# Probe-Scope_AFE_v1_0.net
KiCad netlist of a schematic drawn in Altium Designer
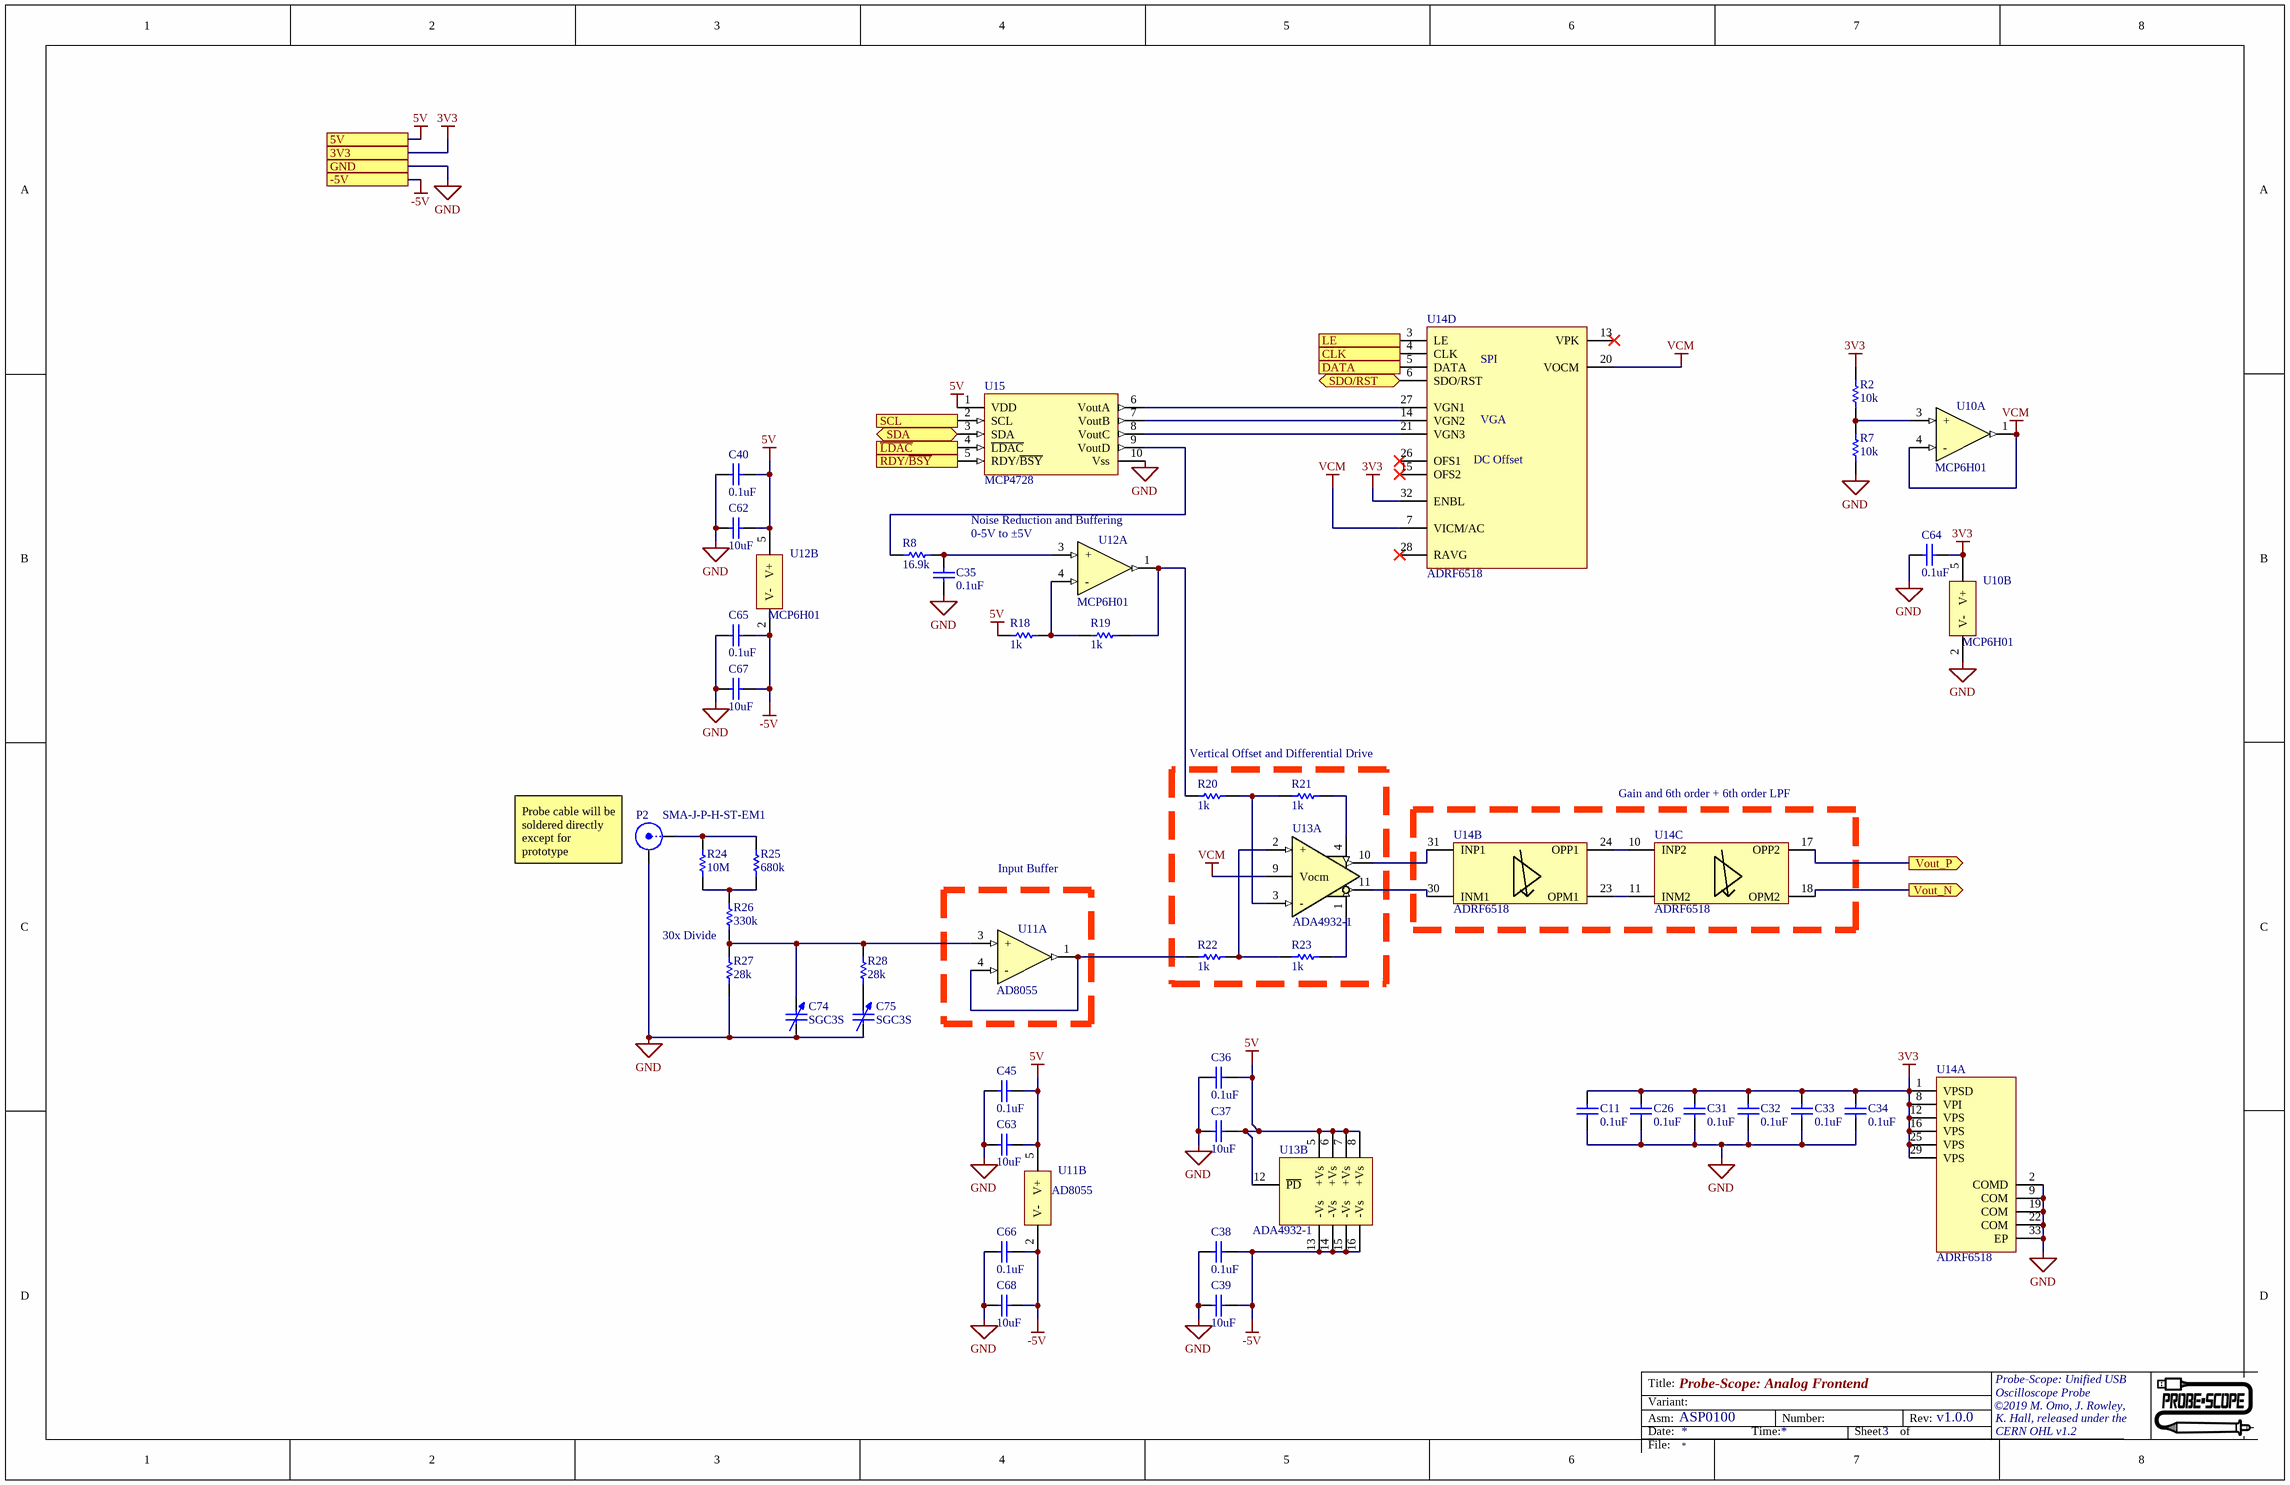
[diagram p0: Probe-Scope AFE v1.0.SchDoc]

(export (version "E")
  (design (tool "Eeschema 10.0.6"))
  (components
    (comp (ref "C11")
      (value "0.1uF")
      (footprint "0402(1005)")
      (fields
        (field (name "MANF") "Samsung Electro-Mechanics")
        (field (name "TOLERANCE") "10")
        (field (name "VOLTAGE") "6.3")
        (field (name "MODIFIED BY") "jrowley")
        (field (name "APPROVED") "False")
      )
      (libsource (lib "MENG Database Library VPN") (part "Cap"))
    )
    (comp (ref "C26")
      (value "0.1uF")
      (footprint "0402(1005)")
      (fields
        (field (name "MANF") "Samsung Electro-Mechanics")
        (field (name "TOLERANCE") "10")
        (field (name "VOLTAGE") "6.3")
        (field (name "MODIFIED BY") "jrowley")
        (field (name "APPROVED") "False")
      )
      (libsource (lib "MENG Database Library VPN") (part "Cap"))
    )
    (comp (ref "C31")
      (value "0.1uF")
      (footprint "0402(1005)")
      (fields
        (field (name "MANF") "Samsung Electro-Mechanics")
        (field (name "TOLERANCE") "10")
        (field (name "VOLTAGE") "6.3")
        (field (name "MODIFIED BY") "jrowley")
        (field (name "APPROVED") "False")
      )
      (libsource (lib "MENG Database Library VPN") (part "Cap"))
    )
    (comp (ref "C32")
      (value "0.1uF")
      (footprint "0402(1005)")
      (fields
        (field (name "MANF") "Samsung Electro-Mechanics")
        (field (name "TOLERANCE") "10")
        (field (name "VOLTAGE") "6.3")
        (field (name "MODIFIED BY") "jrowley")
        (field (name "APPROVED") "False")
      )
      (libsource (lib "MENG Database Library VPN") (part "Cap"))
    )
    (comp (ref "C33")
      (value "0.1uF")
      (footprint "0402(1005)")
      (fields
        (field (name "MANF") "Samsung Electro-Mechanics")
        (field (name "TOLERANCE") "10")
        (field (name "VOLTAGE") "6.3")
        (field (name "MODIFIED BY") "jrowley")
        (field (name "APPROVED") "False")
      )
      (libsource (lib "MENG Database Library VPN") (part "Cap"))
    )
    (comp (ref "C34")
      (value "0.1uF")
      (footprint "0402(1005)")
      (fields
        (field (name "MANF") "Samsung Electro-Mechanics")
        (field (name "TOLERANCE") "10")
        (field (name "VOLTAGE") "6.3")
        (field (name "MODIFIED BY") "jrowley")
        (field (name "APPROVED") "False")
      )
      (libsource (lib "MENG Database Library VPN") (part "Cap"))
    )
    (comp (ref "C35")
      (value "0.1uF")
      (footprint "0402(1005)")
      (fields
        (field (name "MANF") "Samsung Electro-Mechanics")
        (field (name "TOLERANCE") "10")
        (field (name "VOLTAGE") "6.3")
        (field (name "MODIFIED BY") "jrowley")
        (field (name "APPROVED") "False")
      )
      (libsource (lib "MENG Database Library VPN") (part "Cap"))
    )
    (comp (ref "C36")
      (value "0.1uF")
      (footprint "0402(1005)")
      (fields
        (field (name "MANF") "Samsung Electro-Mechanics")
        (field (name "TOLERANCE") "10")
        (field (name "VOLTAGE") "6.3")
        (field (name "MODIFIED BY") "jrowley")
        (field (name "APPROVED") "False")
      )
      (libsource (lib "MENG Database Library VPN") (part "Cap"))
    )
    (comp (ref "C37")
      (value "10uF")
      (footprint "0603(1608)")
      (fields
        (field (name "MANF") "Samsung Electro-Mechanics")
        (field (name "TOLERANCE") "20")
        (field (name "VOLTAGE") "25")
        (field (name "MODIFIED BY") "sotterbacher")
        (field (name "APPROVED") "True")
      )
      (libsource (lib "MENG Database Library VPN") (part "Cap"))
    )
    (comp (ref "C38")
      (value "0.1uF")
      (footprint "0402(1005)")
      (fields
        (field (name "MANF") "Samsung Electro-Mechanics")
        (field (name "TOLERANCE") "10")
        (field (name "VOLTAGE") "6.3")
        (field (name "MODIFIED BY") "jrowley")
        (field (name "APPROVED") "False")
      )
      (libsource (lib "MENG Database Library VPN") (part "Cap"))
    )
    (comp (ref "C39")
      (value "10uF")
      (footprint "0603(1608)")
      (fields
        (field (name "MANF") "Samsung Electro-Mechanics")
        (field (name "TOLERANCE") "20")
        (field (name "VOLTAGE") "25")
        (field (name "MODIFIED BY") "sotterbacher")
        (field (name "APPROVED") "True")
      )
      (libsource (lib "MENG Database Library VPN") (part "Cap"))
    )
    (comp (ref "C40")
      (value "0.1uF")
      (footprint "0402(1005)")
      (fields
        (field (name "MANF") "Samsung Electro-Mechanics")
        (field (name "TOLERANCE") "10")
        (field (name "VOLTAGE") "6.3")
        (field (name "MODIFIED BY") "jrowley")
        (field (name "APPROVED") "False")
      )
      (libsource (lib "MENG Database Library VPN") (part "Cap"))
    )
    (comp (ref "C45")
      (value "0.1uF")
      (footprint "0402(1005)")
      (fields
        (field (name "MANF") "Samsung Electro-Mechanics")
        (field (name "TOLERANCE") "10")
        (field (name "VOLTAGE") "6.3")
        (field (name "MODIFIED BY") "jrowley")
        (field (name "APPROVED") "False")
      )
      (libsource (lib "MENG Database Library VPN") (part "Cap"))
    )
    (comp (ref "C62")
      (value "10uF")
      (footprint "0603(1608)")
      (fields
        (field (name "MANF") "Samsung Electro-Mechanics")
        (field (name "TOLERANCE") "20")
        (field (name "VOLTAGE") "25")
        (field (name "MODIFIED BY") "sotterbacher")
        (field (name "APPROVED") "True")
      )
      (libsource (lib "MENG Database Library VPN") (part "Cap"))
    )
    (comp (ref "C63")
      (value "10uF")
      (footprint "0603(1608)")
      (fields
        (field (name "MANF") "Samsung Electro-Mechanics")
        (field (name "TOLERANCE") "20")
        (field (name "VOLTAGE") "25")
        (field (name "MODIFIED BY") "sotterbacher")
        (field (name "APPROVED") "True")
      )
      (libsource (lib "MENG Database Library VPN") (part "Cap"))
    )
    (comp (ref "C64")
      (value "0.1uF")
      (footprint "0402(1005)")
      (fields
        (field (name "MANF") "Samsung Electro-Mechanics")
        (field (name "TOLERANCE") "10")
        (field (name "VOLTAGE") "6.3")
        (field (name "MODIFIED BY") "jrowley")
        (field (name "APPROVED") "False")
      )
      (libsource (lib "MENG Database Library VPN") (part "Cap"))
    )
    (comp (ref "C65")
      (value "0.1uF")
      (footprint "0402(1005)")
      (fields
        (field (name "MANF") "Samsung Electro-Mechanics")
        (field (name "TOLERANCE") "10")
        (field (name "VOLTAGE") "6.3")
        (field (name "MODIFIED BY") "jrowley")
        (field (name "APPROVED") "False")
      )
      (libsource (lib "MENG Database Library VPN") (part "Cap"))
    )
    (comp (ref "C66")
      (value "0.1uF")
      (footprint "0402(1005)")
      (fields
        (field (name "MANF") "Samsung Electro-Mechanics")
        (field (name "TOLERANCE") "10")
        (field (name "VOLTAGE") "6.3")
        (field (name "MODIFIED BY") "jrowley")
        (field (name "APPROVED") "False")
      )
      (libsource (lib "MENG Database Library VPN") (part "Cap"))
    )
    (comp (ref "C67")
      (value "10uF")
      (footprint "0603(1608)")
      (fields
        (field (name "MANF") "Samsung Electro-Mechanics")
        (field (name "TOLERANCE") "20")
        (field (name "VOLTAGE") "25")
        (field (name "MODIFIED BY") "sotterbacher")
        (field (name "APPROVED") "True")
      )
      (libsource (lib "MENG Database Library VPN") (part "Cap"))
    )
    (comp (ref "C68")
      (value "10uF")
      (footprint "0603(1608)")
      (fields
        (field (name "MANF") "Samsung Electro-Mechanics")
        (field (name "TOLERANCE") "20")
        (field (name "VOLTAGE") "25")
        (field (name "MODIFIED BY") "sotterbacher")
        (field (name "APPROVED") "True")
      )
      (libsource (lib "MENG Database Library VPN") (part "Cap"))
    )
    (comp (ref "C74") (value "SGC3S") (footprint "SGC3S") (libsource (lib "SE2D v1.0") (part "VarCap")))
    (comp (ref "C75") (value "SGC3S") (footprint "SGC3S") (libsource (lib "SE2D v1.0") (part "VarCap")))
    (comp (ref "P2")
      (value "SMA-J-P-H-ST-EM1")
      (footprint "SE2D v1.0:*SMA-J-P-H-ST-EM1_SMA-J-P-H-ST-EM1(Primary)")
      (fields (field (name "MANF") "Samtec Inc."))
      (libsource (lib "SE2D v1.0") (part "SMA-J-P-H-ST-EM1"))
    )
    (comp (ref "R2")
      (value "10k")
      (footprint "0402(1005)")
      (fields
        (field (name "MANF") "Stackpole Electronics")
        (field (name "TOLERANCE") "1")
        (field (name "POWER") "0.0625")
        (field (name "MODIFIED BY") "jrowley")
        (field (name "APPROVED") "False")
      )
      (libsource (lib "MENG Database Library VPN") (part "Res1"))
    )
    (comp (ref "R7")
      (value "10k")
      (footprint "0402(1005)")
      (fields
        (field (name "MANF") "Stackpole Electronics")
        (field (name "TOLERANCE") "1")
        (field (name "POWER") "0.0625")
        (field (name "MODIFIED BY") "jrowley")
        (field (name "APPROVED") "False")
      )
      (libsource (lib "MENG Database Library VPN") (part "Res1"))
    )
    (comp (ref "R8")
      (value "16.9k")
      (footprint "0603(1608)")
      (fields
        (field (name "MANF") "Panasonic")
        (field (name "TOLERANCE") "1")
        (field (name "POWER") "0.1")
        (field (name "MODIFIED BY") "sotterbacher")
        (field (name "APPROVED") "True")
      )
      (libsource (lib "MENG Database Library VPN") (part "Res1"))
    )
    (comp (ref "R18")
      (value "1k")
      (footprint "0402(1005)")
      (fields
        (field (name "MANF") "Yageo")
        (field (name "TOLERANCE") "1")
        (field (name "POWER") "0.063")
        (field (name "MODIFIED BY") "jrowley")
        (field (name "APPROVED") "False")
      )
      (libsource (lib "MENG Database Library VPN") (part "Res1"))
    )
    (comp (ref "R19")
      (value "1k")
      (footprint "0402(1005)")
      (fields
        (field (name "MANF") "Yageo")
        (field (name "TOLERANCE") "1")
        (field (name "POWER") "0.063")
        (field (name "MODIFIED BY") "jrowley")
        (field (name "APPROVED") "False")
      )
      (libsource (lib "MENG Database Library VPN") (part "Res1"))
    )
    (comp (ref "R20")
      (value "1k")
      (footprint "0402(1005)")
      (fields
        (field (name "MANF") "Yageo")
        (field (name "TOLERANCE") "1")
        (field (name "POWER") "0.063")
        (field (name "MODIFIED BY") "jrowley")
        (field (name "APPROVED") "False")
      )
      (libsource (lib "MENG Database Library VPN") (part "Res1"))
    )
    (comp (ref "R21")
      (value "1k")
      (footprint "0402(1005)")
      (fields
        (field (name "MANF") "Yageo")
        (field (name "TOLERANCE") "1")
        (field (name "POWER") "0.063")
        (field (name "MODIFIED BY") "jrowley")
        (field (name "APPROVED") "False")
      )
      (libsource (lib "MENG Database Library VPN") (part "Res1"))
    )
    (comp (ref "R22")
      (value "1k")
      (footprint "0402(1005)")
      (fields
        (field (name "MANF") "Yageo")
        (field (name "TOLERANCE") "1")
        (field (name "POWER") "0.063")
        (field (name "MODIFIED BY") "jrowley")
        (field (name "APPROVED") "False")
      )
      (libsource (lib "MENG Database Library VPN") (part "Res1"))
    )
    (comp (ref "R23")
      (value "1k")
      (footprint "0402(1005)")
      (fields
        (field (name "MANF") "Yageo")
        (field (name "TOLERANCE") "1")
        (field (name "POWER") "0.063")
        (field (name "MODIFIED BY") "jrowley")
        (field (name "APPROVED") "False")
      )
      (libsource (lib "MENG Database Library VPN") (part "Res1"))
    )
    (comp (ref "R24")
      (value "10M")
      (footprint "0402(1005)")
      (fields
        (field (name "MANF") "Vishay Dale")
        (field (name "TOLERANCE") "1")
        (field (name "POWER") "0.063")
        (field (name "MODIFIED BY") "momo")
        (field (name "APPROVED") "False")
      )
      (libsource (lib "MENG Database Library VPN") (part "Res1"))
    )
    (comp (ref "R25")
      (value "680k")
      (footprint "0402(1005)")
      (fields
        (field (name "MANF") "Vishay Dale")
        (field (name "TOLERANCE") "1")
        (field (name "POWER") "0.063")
        (field (name "MODIFIED BY") "momo")
        (field (name "APPROVED") "False")
      )
      (libsource (lib "MENG Database Library VPN") (part "Res1"))
    )
    (comp (ref "R26")
      (value "330k")
      (footprint "0402(1005)")
      (fields
        (field (name "MANF") "Vishay Dale")
        (field (name "TOLERANCE") "1")
        (field (name "POWER") "0.2")
        (field (name "MODIFIED BY") "momo")
        (field (name "APPROVED") "False")
      )
      (libsource (lib "MENG Database Library VPN") (part "Res1"))
    )
    (comp (ref "R27")
      (value "28k")
      (footprint "0402(1005)")
      (fields
        (field (name "MANF") "Vishay Dale")
        (field (name "TOLERANCE") "1")
        (field (name "POWER") "0.063")
        (field (name "MODIFIED BY") "momo")
        (field (name "APPROVED") "False")
      )
      (libsource (lib "MENG Database Library VPN") (part "Res1"))
    )
    (comp (ref "R28")
      (value "28k")
      (footprint "0402(1005)")
      (fields
        (field (name "MANF") "Vishay Dale")
        (field (name "TOLERANCE") "1")
        (field (name "POWER") "0.063")
        (field (name "MODIFIED BY") "momo")
        (field (name "APPROVED") "False")
      )
      (libsource (lib "MENG Database Library VPN") (part "Res1"))
    )
    (comp (ref "U10")
      (value "MCP6H01")
      (footprint "SOT23-5")
      (fields
        (field (name "MANF") "Microchip")
        (field (name "MODIFIED BY") "momo")
        (field (name "APPROVED") "False")
      )
      (libsource (lib "MENG Database Library VPN") (part "Opamp Single SOT23-5"))
    )
    (comp (ref "U11")
      (value "AD8055")
      (footprint "SOT95P280X145-5L")
      (fields (field (name "MANF") "Analog Devices Inc."))
      (libsource (lib "PS v1.0") (part "AD8055"))
    )
    (comp (ref "U12")
      (value "MCP6H01")
      (footprint "SOT23-5")
      (fields
        (field (name "MANF") "Microchip")
        (field (name "MODIFIED BY") "momo")
        (field (name "APPROVED") "False")
      )
      (libsource (lib "MENG Database Library VPN") (part "Opamp Single SOT23-5"))
    )
    (comp (ref "U13")
      (value "ADA4932-1")
      (footprint "QFN50P300X300X80_HS-17L")
      (fields (field (name "MANF") "Analog Devices Inc."))
      (libsource (lib "PS v1.0") (part "ADA4932"))
    )
    (comp (ref "U14")
      (value "ADRF6518")
      (footprint "QFN50P500X500X80_HS-33L")
      (fields (field (name "MANF") "Analog Devices Inc."))
      (libsource (lib "PS v1.0") (part "ADRF6518"))
    )
    (comp (ref "U15")
      (value "MCP4728")
      (footprint "MSOP-10")
      (fields (field (name "MANF") "Microchip Technology"))
      (libsource (lib "PS v1.0") (part "MCP4728"))
    )
  )
  (nets
    (net (code "1") (name "-5V") (class "Default")
      (node (ref "C38") (pin "2") (pinfunction "2_2") (pintype "passive"))
      (node (ref "C39") (pin "2") (pinfunction "2_2") (pintype "passive"))
      (node (ref "C65") (pin "2") (pinfunction "2_2") (pintype "passive"))
      (node (ref "C66") (pin "2") (pinfunction "2_2") (pintype "passive"))
      (node (ref "C67") (pin "2") (pinfunction "2_2") (pintype "passive"))
      (node (ref "C68") (pin "2") (pinfunction "2_2") (pintype "passive"))
      (node (ref "U11") (pin "2") (pinfunction "V-_2") (pintype "power_in"))
      (node (ref "U12") (pin "2") (pinfunction "V-_2") (pintype "power_in"))
      (node (ref "U13") (pin "13") (pinfunction "-Vs_13") (pintype "power_in"))
      (node (ref "U13") (pin "14") (pinfunction "-Vs_14") (pintype "power_in"))
      (node (ref "U13") (pin "15") (pinfunction "-Vs_15") (pintype "power_in"))
      (node (ref "U13") (pin "16") (pinfunction "-Vs_16") (pintype "power_in"))
    )
    (net (code "2") (name "/CLK") (class "Default")
      (node (ref "U14") (pin "4") (pinfunction "CLK_4") (pintype "passive"))
    )
    (net (code "3") (name "/DATA") (class "Default")
      (node (ref "U14") (pin "5") (pinfunction "DATA_5") (pintype "passive"))
    )
    (net (code "4") (name "/LE") (class "Default")
      (node (ref "U14") (pin "3") (pinfunction "LE_3") (pintype "passive"))
    )
    (net (code "5") (name "/RDY{slash}~{BSY}") (class "Default")
      (node (ref "U15") (pin "5") (pinfunction "RDY/~{BSY}_5") (pintype "input"))
    )
    (net (code "6") (name "/SCL") (class "Default")
      (node (ref "U15") (pin "2") (pinfunction "SCL_2") (pintype "input"))
    )
    (net (code "7") (name "/SDA") (class "Default")
      (node (ref "U15") (pin "3") (pinfunction "SDA_3") (pintype "input"))
    )
    (net (code "8") (name "/SDO{slash}RST") (class "Default")
      (node (ref "U14") (pin "6") (pinfunction "SDO/RST_6") (pintype "passive"))
    )
    (net (code "9") (name "/Vout_N") (class "Default")
      (node (ref "U14") (pin "18") (pinfunction "OPM2_18") (pintype "passive"))
    )
    (net (code "10") (name "/Vout_P") (class "Default")
      (node (ref "U14") (pin "17") (pinfunction "OPP2_17") (pintype "passive"))
    )
    (net (code "11") (name "/~{LDAC}") (class "Default")
      (node (ref "U15") (pin "4") (pinfunction "~{LDAC}_4") (pintype "input"))
    )
    (net (code "12") (name "3V3") (class "Default")
      (node (ref "C11") (pin "2") (pinfunction "2_2") (pintype "passive"))
      (node (ref "C26") (pin "2") (pinfunction "2_2") (pintype "passive"))
      (node (ref "C31") (pin "2") (pinfunction "2_2") (pintype "passive"))
      (node (ref "C32") (pin "2") (pinfunction "2_2") (pintype "passive"))
      (node (ref "C33") (pin "2") (pinfunction "2_2") (pintype "passive"))
      (node (ref "C34") (pin "2") (pinfunction "2_2") (pintype "passive"))
      (node (ref "C64") (pin "2") (pinfunction "2_2") (pintype "passive"))
      (node (ref "R2") (pin "2") (pinfunction "2_2") (pintype "passive"))
      (node (ref "U10") (pin "5") (pinfunction "V+_5") (pintype "power_in"))
      (node (ref "U14") (pin "1") (pinfunction "VPSD_1") (pintype "passive"))
      (node (ref "U14") (pin "12") (pinfunction "VPS_12") (pintype "passive"))
      (node (ref "U14") (pin "16") (pinfunction "VPS_16") (pintype "passive"))
      (node (ref "U14") (pin "25") (pinfunction "VPS_25") (pintype "passive"))
      (node (ref "U14") (pin "29") (pinfunction "VPS_29") (pintype "passive"))
      (node (ref "U14") (pin "32") (pinfunction "ENBL_32") (pintype "passive"))
      (node (ref "U14") (pin "8") (pinfunction "VPI_8") (pintype "passive"))
    )
    (net (code "13") (name "5V") (class "Default")
      (node (ref "C36") (pin "2") (pinfunction "2_2") (pintype "passive"))
      (node (ref "C37") (pin "2") (pinfunction "2_2") (pintype "passive"))
      (node (ref "C40") (pin "2") (pinfunction "2_2") (pintype "passive"))
      (node (ref "C45") (pin "2") (pinfunction "2_2") (pintype "passive"))
      (node (ref "C62") (pin "2") (pinfunction "2_2") (pintype "passive"))
      (node (ref "C63") (pin "2") (pinfunction "2_2") (pintype "passive"))
      (node (ref "R18") (pin "1") (pinfunction "1_1") (pintype "passive"))
      (node (ref "U11") (pin "5") (pinfunction "V+_5") (pintype "power_in"))
      (node (ref "U12") (pin "5") (pinfunction "V+_5") (pintype "power_in"))
      (node (ref "U13") (pin "12") (pinfunction "~{PD}_12") (pintype "power_in"))
      (node (ref "U13") (pin "5") (pinfunction "+Vs_5") (pintype "power_in"))
      (node (ref "U13") (pin "6") (pinfunction "+Vs_6") (pintype "power_in"))
      (node (ref "U13") (pin "7") (pinfunction "+Vs_7") (pintype "power_in"))
      (node (ref "U13") (pin "8") (pinfunction "+Vs_8") (pintype "power_in"))
      (node (ref "U15") (pin "1") (pinfunction "VDD_1") (pintype "power_in"))
    )
    (net (code "14") (name "GND") (class "Default")
      (node (ref "C11") (pin "1") (pinfunction "1_1") (pintype "passive"))
      (node (ref "C26") (pin "1") (pinfunction "1_1") (pintype "passive"))
      (node (ref "C31") (pin "1") (pinfunction "1_1") (pintype "passive"))
      (node (ref "C32") (pin "1") (pinfunction "1_1") (pintype "passive"))
      (node (ref "C33") (pin "1") (pinfunction "1_1") (pintype "passive"))
      (node (ref "C34") (pin "1") (pinfunction "1_1") (pintype "passive"))
      (node (ref "C35") (pin "1") (pinfunction "1_1") (pintype "passive"))
      (node (ref "C36") (pin "1") (pinfunction "1_1") (pintype "passive"))
      (node (ref "C37") (pin "1") (pinfunction "1_1") (pintype "passive"))
      (node (ref "C38") (pin "1") (pinfunction "1_1") (pintype "passive"))
      (node (ref "C39") (pin "1") (pinfunction "1_1") (pintype "passive"))
      (node (ref "C40") (pin "1") (pinfunction "1_1") (pintype "passive"))
      (node (ref "C45") (pin "1") (pinfunction "1_1") (pintype "passive"))
      (node (ref "C62") (pin "1") (pinfunction "1_1") (pintype "passive"))
      (node (ref "C63") (pin "1") (pinfunction "1_1") (pintype "passive"))
      (node (ref "C64") (pin "1") (pinfunction "1_1") (pintype "passive"))
      (node (ref "C65") (pin "1") (pinfunction "1_1") (pintype "passive"))
      (node (ref "C66") (pin "1") (pinfunction "1_1") (pintype "passive"))
      (node (ref "C67") (pin "1") (pinfunction "1_1") (pintype "passive"))
      (node (ref "C68") (pin "1") (pinfunction "1_1") (pintype "passive"))
      (node (ref "C74") (pin "1") (pintype "passive"))
      (node (ref "C75") (pin "1") (pintype "passive"))
      (node (ref "P2") (pin "2") (pinfunction "Y_2") (pintype "passive"))
      (node (ref "R27") (pin "1") (pinfunction "1_1") (pintype "passive"))
      (node (ref "R7") (pin "1") (pinfunction "1_1") (pintype "passive"))
      (node (ref "U10") (pin "2") (pinfunction "V-_2") (pintype "power_in"))
      (node (ref "U14") (pin "19") (pinfunction "COM_19") (pintype "passive"))
      (node (ref "U14") (pin "2") (pinfunction "COMD_2") (pintype "passive"))
      (node (ref "U14") (pin "22") (pinfunction "COM_22") (pintype "passive"))
      (node (ref "U14") (pin "33") (pinfunction "EP_33") (pintype "passive"))
      (node (ref "U14") (pin "9") (pinfunction "COM_9") (pintype "passive"))
      (node (ref "U15") (pin "10") (pinfunction "Vss_10") (pintype "power_in"))
    )
    (net (code "15") (name "Net-(C75-Pad2)") (class "Default")
      (node (ref "C75") (pin "2") (pintype "passive"))
      (node (ref "R28") (pin "1") (pinfunction "1_1") (pintype "passive"))
    )
    (net (code "16") (name "Net-(P2-X)") (class "Default")
      (node (ref "P2") (pin "1") (pinfunction "X_1") (pintype "passive"))
      (node (ref "R24") (pin "2") (pinfunction "2_2") (pintype "passive"))
      (node (ref "R25") (pin "2") (pinfunction "2_2") (pintype "passive"))
    )
    (net (code "17") (name "Net-(R24-Pad1)") (class "Default")
      (node (ref "R24") (pin "1") (pinfunction "1_1") (pintype "passive"))
      (node (ref "R25") (pin "1") (pinfunction "1_1") (pintype "passive"))
      (node (ref "R26") (pin "2") (pinfunction "2_2") (pintype "passive"))
    )
    (net (code "18") (name "Net-(U10A-+)") (class "Default")
      (node (ref "R2") (pin "1") (pinfunction "1_1") (pintype "passive"))
      (node (ref "R7") (pin "2") (pinfunction "2_2") (pintype "passive"))
      (node (ref "U10") (pin "3") (pinfunction "+_3") (pintype "input"))
    )
    (net (code "19") (name "Net-(U11A-+)") (class "Default")
      (node (ref "C74") (pin "2") (pintype "passive"))
      (node (ref "R26") (pin "1") (pinfunction "1_1") (pintype "passive"))
      (node (ref "R27") (pin "2") (pinfunction "2_2") (pintype "passive"))
      (node (ref "R28") (pin "2") (pinfunction "2_2") (pintype "passive"))
      (node (ref "U11") (pin "3") (pinfunction "+_3") (pintype "input"))
    )
    (net (code "20") (name "Net-(U11A--)") (class "Default")
      (node (ref "R22") (pin "1") (pinfunction "1_1") (pintype "passive"))
      (node (ref "U11") (pin "1") (pinfunction "OUT_1") (pintype "output"))
      (node (ref "U11") (pin "4") (pinfunction "-_4") (pintype "input"))
    )
    (net (code "21") (name "Net-(U12A-+)") (class "Default")
      (node (ref "C35") (pin "2") (pinfunction "2_2") (pintype "passive"))
      (node (ref "R8") (pin "2") (pinfunction "2_2") (pintype "passive"))
      (node (ref "U12") (pin "3") (pinfunction "+_3") (pintype "input"))
    )
    (net (code "22") (name "Net-(U12A--)") (class "Default")
      (node (ref "R18") (pin "2") (pinfunction "2_2") (pintype "passive"))
      (node (ref "R19") (pin "1") (pinfunction "1_1") (pintype "passive"))
      (node (ref "U12") (pin "4") (pinfunction "-_4") (pintype "input"))
    )
    (net (code "23") (name "Net-(U12A-OUT)") (class "Default")
      (node (ref "R19") (pin "2") (pinfunction "2_2") (pintype "passive"))
      (node (ref "R20") (pin "1") (pinfunction "1_1") (pintype "passive"))
      (node (ref "U12") (pin "1") (pinfunction "OUT_1") (pintype "output"))
    )
    (net (code "24") (name "Net-(U13A-+)") (class "Default")
      (node (ref "R22") (pin "2") (pinfunction "2_2") (pintype "passive"))
      (node (ref "R23") (pin "1") (pinfunction "1_1") (pintype "passive"))
      (node (ref "U13") (pin "2") (pinfunction "+_2") (pintype "input"))
    )
    (net (code "25") (name "Net-(U13A-+FB)") (class "Default")
      (node (ref "R21") (pin "2") (pinfunction "2_2") (pintype "passive"))
      (node (ref "U13") (pin "4") (pinfunction "+FB_4") (pintype "input"))
    )
    (net (code "26") (name "Net-(U13A-+out)") (class "Default")
      (node (ref "U13") (pin "10") (pinfunction "+out_10") (pintype "output"))
      (node (ref "U14") (pin "31") (pinfunction "INP1_31") (pintype "passive"))
    )
    (net (code "27") (name "Net-(U13A--)") (class "Default")
      (node (ref "R20") (pin "2") (pinfunction "2_2") (pintype "passive"))
      (node (ref "R21") (pin "1") (pinfunction "1_1") (pintype "passive"))
      (node (ref "U13") (pin "3") (pinfunction "-_3") (pintype "input"))
    )
    (net (code "28") (name "Net-(U13A--FB)") (class "Default")
      (node (ref "R23") (pin "2") (pinfunction "2_2") (pintype "passive"))
      (node (ref "U13") (pin "1") (pinfunction "-FB_1") (pintype "input"))
    )
    (net (code "29") (name "Net-(U13A--Out)") (class "Default")
      (node (ref "U13") (pin "11") (pinfunction "-Out_11") (pintype "output"))
      (node (ref "U14") (pin "30") (pinfunction "INM1_30") (pintype "passive"))
    )
    (net (code "30") (name "Net-(U14B-OPM1)") (class "Default")
      (node (ref "U14") (pin "11") (pinfunction "INM2_11") (pintype "passive"))
      (node (ref "U14") (pin "23") (pinfunction "OPM1_23") (pintype "passive"))
    )
    (net (code "31") (name "Net-(U14B-OPP1)") (class "Default")
      (node (ref "U14") (pin "10") (pinfunction "INP2_10") (pintype "passive"))
      (node (ref "U14") (pin "24") (pinfunction "OPP1_24") (pintype "passive"))
    )
    (net (code "32") (name "Net-(U14D-VGN1)") (class "Default")
      (node (ref "U14") (pin "27") (pinfunction "VGN1_27") (pintype "passive"))
      (node (ref "U15") (pin "6") (pinfunction "VoutA_6") (pintype "output"))
    )
    (net (code "33") (name "Net-(U14D-VGN2)") (class "Default")
      (node (ref "U14") (pin "14") (pinfunction "VGN2_14") (pintype "passive"))
      (node (ref "U15") (pin "7") (pinfunction "VoutB_7") (pintype "output"))
    )
    (net (code "34") (name "Net-(U14D-VGN3)") (class "Default")
      (node (ref "U14") (pin "21") (pinfunction "VGN3_21") (pintype "passive"))
      (node (ref "U15") (pin "8") (pinfunction "VoutC_8") (pintype "output"))
    )
    (net (code "35") (name "Net-(U15-VoutD)") (class "Default")
      (node (ref "R8") (pin "1") (pinfunction "1_1") (pintype "passive"))
      (node (ref "U15") (pin "9") (pinfunction "VoutD_9") (pintype "output"))
    )
    (net (code "36") (name "VCM") (class "Default")
      (node (ref "U10") (pin "1") (pinfunction "OUT_1") (pintype "output"))
      (node (ref "U10") (pin "4") (pinfunction "-_4") (pintype "input"))
      (node (ref "U13") (pin "9") (pinfunction "Vocm_9") (pintype "passive"))
      (node (ref "U14") (pin "20") (pinfunction "VOCM_20") (pintype "passive"))
      (node (ref "U14") (pin "7") (pinfunction "VICM/AC_7") (pintype "passive"))
    )
    (net (code "37") (name "unconnected-(U14D-OFS1-Pad26)") (class "Default")
      (node (ref "U14") (pin "26") (pinfunction "OFS1_26") (pintype "passive+no_connect"))
    )
    (net (code "38") (name "unconnected-(U14D-OFS2-Pad15)") (class "Default")
      (node (ref "U14") (pin "15") (pinfunction "OFS2_15") (pintype "passive+no_connect"))
    )
    (net (code "39") (name "unconnected-(U14D-RAVG-Pad28)") (class "Default")
      (node (ref "U14") (pin "28") (pinfunction "RAVG_28") (pintype "passive+no_connect"))
    )
    (net (code "40") (name "unconnected-(U14D-VPK-Pad13)") (class "Default")
      (node (ref "U14") (pin "13") (pinfunction "VPK_13") (pintype "passive+no_connect"))
    )
  )
)
